# 0_96_OLED_FOR_1U.net
KiCad netlist of a schematic drawn in EAGLE
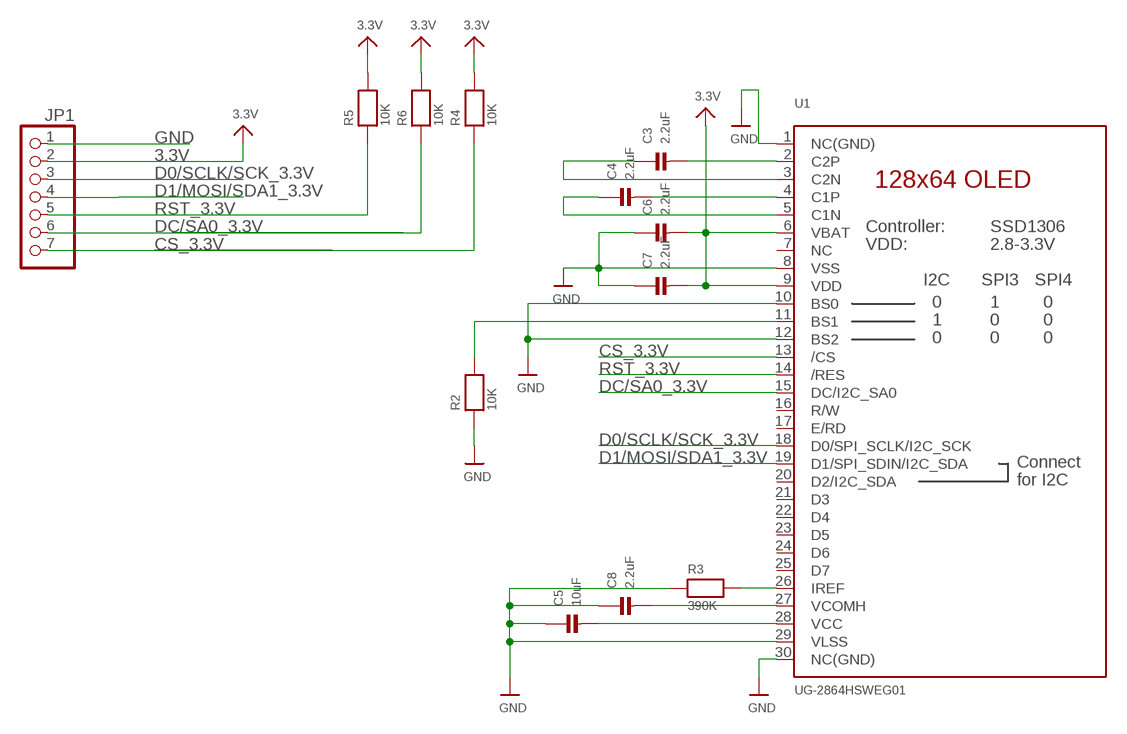
[diagram p0: schematic, sheet 1]

(export (version "E")
  (design (tool "Eeschema 10.0.6"))
  (components
    (comp (ref "C3")
      (value "2.2uF")
      (footprint "eagle-import:0603-MINI")
      (libsource (lib "eagle-import") (part "CAP_CERAMIC0603MINI"))
    )
    (comp (ref "C4")
      (value "2.2uF")
      (footprint "eagle-import:0603-MINI")
      (libsource (lib "eagle-import") (part "CAP_CERAMIC0603MINI"))
    )
    (comp (ref "C5")
      (value "10uF")
      (footprint "eagle-import:0603-MINI")
      (libsource (lib "eagle-import") (part "CAP_CERAMIC0603MINI"))
    )
    (comp (ref "C6")
      (value "2.2uF")
      (footprint "eagle-import:0603-MINI")
      (libsource (lib "eagle-import") (part "CAP_CERAMIC0603MINI"))
    )
    (comp (ref "C7")
      (value "2.2uF")
      (footprint "eagle-import:0603-MINI")
      (libsource (lib "eagle-import") (part "CAP_CERAMIC0603MINI"))
    )
    (comp (ref "C8")
      (value "2.2uF")
      (footprint "eagle-import:0603-MINI")
      (libsource (lib "eagle-import") (part "CAP_CERAMIC0603MINI"))
    )
    (comp (ref "JP1")
      (value "HEADER-1X7ROUND")
      (footprint "eagle-import:1X07_ROUND")
      (fields (field (name "SPICEPREFIX") "X"))
      (libsource (lib "eagle-import") (part "HEADER-1X7ROUND"))
    )
    (comp (ref "R2")
      (value "10K")
      (footprint "eagle-import:0603-MINI")
      (libsource (lib "eagle-import") (part "RESISTOR0603MINI"))
    )
    (comp (ref "R3")
      (value "390K")
      (footprint "eagle-import:0603-MINI")
      (libsource (lib "eagle-import") (part "RESISTOR0603MINI"))
    )
    (comp (ref "R4")
      (value "10K")
      (footprint "eagle-import:0603-MINI")
      (libsource (lib "eagle-import") (part "RESISTOR0603MINI"))
    )
    (comp (ref "R5")
      (value "10K")
      (footprint "eagle-import:0603-MINI")
      (libsource (lib "eagle-import") (part "RESISTOR0603MINI"))
    )
    (comp (ref "R6")
      (value "10K")
      (footprint "eagle-import:0603-MINI")
      (libsource (lib "eagle-import") (part "RESISTOR0603MINI"))
    )
    (comp (ref "U1")
      (value "UG-2864HSWEG01")
      (footprint "eagle-import:MICROBUILDER_UG-2864HSWEG01_0.96IN_WRAPAROUND")
      (libsource (lib "eagle-import") (part "MICROBUILDER_DISP_OLED_UG-2864HSWEG010.96{dblquote}"))
    )
  )
  (nets
    (net (code "1") (name "/CS_3.3V") (class "Default")
      (node (ref "JP1") (pin "7") (pinfunction "7_7") (pintype "passive"))
      (node (ref "R4") (pin "1") (pinfunction "1_1") (pintype "passive"))
      (node (ref "U1") (pin "13") (pinfunction "/CS_13") (pintype "input"))
    )
    (net (code "2") (name "/D0{slash}SCLK{slash}SCK_3.3V") (class "Default")
      (node (ref "JP1") (pin "3") (pinfunction "3_3") (pintype "passive"))
      (node (ref "U1") (pin "18") (pinfunction "D0/SPI_SCLK/I2C_SCK_18") (pintype "bidirectional"))
    )
    (net (code "3") (name "/D1{slash}MOSI{slash}SDA1_3.3V") (class "Default")
      (node (ref "JP1") (pin "4") (pinfunction "4_4") (pintype "passive"))
      (node (ref "U1") (pin "19") (pinfunction "D1/SPI_SDIN/I2C_SDA_19") (pintype "bidirectional"))
    )
    (net (code "4") (name "/DC{slash}SA0_3.3V") (class "Default")
      (node (ref "JP1") (pin "6") (pinfunction "6_6") (pintype "passive"))
      (node (ref "R6") (pin "1") (pinfunction "1_1") (pintype "passive"))
      (node (ref "U1") (pin "15") (pinfunction "DC/I2C_SA0_15") (pintype "input"))
    )
    (net (code "5") (name "/RST_3.3V") (class "Default")
      (node (ref "JP1") (pin "5") (pinfunction "5_5") (pintype "passive"))
      (node (ref "R5") (pin "1") (pinfunction "1_1") (pintype "passive"))
      (node (ref "U1") (pin "14") (pinfunction "/RES_14") (pintype "input"))
    )
    (net (code "6") (name "3.3V") (class "Default")
      (node (ref "C6") (pin "2") (pinfunction "P$2_2") (pintype "passive"))
      (node (ref "C7") (pin "2") (pinfunction "P$2_2") (pintype "passive"))
      (node (ref "JP1") (pin "2") (pinfunction "2_2") (pintype "passive"))
      (node (ref "R4") (pin "2") (pinfunction "2_2") (pintype "passive"))
      (node (ref "R5") (pin "2") (pinfunction "2_2") (pintype "passive"))
      (node (ref "R6") (pin "2") (pinfunction "2_2") (pintype "passive"))
      (node (ref "U1") (pin "6") (pinfunction "VBAT_6") (pintype "input"))
      (node (ref "U1") (pin "9") (pinfunction "VDD_9") (pintype "power_in"))
    )
    (net (code "7") (name "GND") (class "Default")
      (node (ref "C5") (pin "1") (pinfunction "P$1_1") (pintype "passive"))
      (node (ref "C6") (pin "1") (pinfunction "P$1_1") (pintype "passive"))
      (node (ref "C7") (pin "1") (pinfunction "P$1_1") (pintype "passive"))
      (node (ref "C8") (pin "1") (pinfunction "P$1_1") (pintype "passive"))
      (node (ref "JP1") (pin "1") (pinfunction "1_1") (pintype "passive"))
      (node (ref "R2") (pin "1") (pinfunction "1_1") (pintype "passive"))
      (node (ref "R3") (pin "1") (pinfunction "1_1") (pintype "passive"))
      (node (ref "U1") (pin "1") (pinfunction "NC(GND)_1") (pintype "input"))
      (node (ref "U1") (pin "10") (pinfunction "BS0_10") (pintype "input"))
      (node (ref "U1") (pin "12") (pinfunction "BS2_12") (pintype "input"))
      (node (ref "U1") (pin "29") (pinfunction "VLSS_29") (pintype "power_in"))
      (node (ref "U1") (pin "30") (pinfunction "NC(GND)_30") (pintype "input"))
      (node (ref "U1") (pin "8") (pinfunction "VSS_8") (pintype "power_in"))
    )
    (net (code "8") (name "Net-(C3-P$1)") (class "Default")
      (node (ref "C3") (pin "1") (pinfunction "P$1_1") (pintype "passive"))
      (node (ref "U1") (pin "3") (pinfunction "C2N_3") (pintype "input"))
    )
    (net (code "9") (name "Net-(C3-P$2)") (class "Default")
      (node (ref "C3") (pin "2") (pinfunction "P$2_2") (pintype "passive"))
      (node (ref "U1") (pin "2") (pinfunction "C2P_2") (pintype "input"))
    )
    (net (code "10") (name "Net-(C4-P$1)") (class "Default")
      (node (ref "C4") (pin "1") (pinfunction "P$1_1") (pintype "passive"))
      (node (ref "U1") (pin "5") (pinfunction "C1N_5") (pintype "input"))
    )
    (net (code "11") (name "Net-(C4-P$2)") (class "Default")
      (node (ref "C4") (pin "2") (pinfunction "P$2_2") (pintype "passive"))
      (node (ref "U1") (pin "4") (pinfunction "C1P_4") (pintype "input"))
    )
    (net (code "12") (name "Net-(C5-P$2)") (class "Default")
      (node (ref "C5") (pin "2") (pinfunction "P$2_2") (pintype "passive"))
      (node (ref "U1") (pin "28") (pinfunction "VCC_28") (pintype "power_in"))
    )
    (net (code "13") (name "Net-(C8-P$2)") (class "Default")
      (node (ref "C8") (pin "2") (pinfunction "P$2_2") (pintype "passive"))
      (node (ref "U1") (pin "27") (pinfunction "VCOMH_27") (pintype "output"))
    )
    (net (code "14") (name "Net-(U1-BS1)") (class "Default")
      (node (ref "R2") (pin "2") (pinfunction "2_2") (pintype "passive"))
      (node (ref "U1") (pin "11") (pinfunction "BS1_11") (pintype "input"))
    )
    (net (code "15") (name "Net-(U1-IREF)") (class "Default")
      (node (ref "R3") (pin "2") (pinfunction "2_2") (pintype "passive"))
      (node (ref "U1") (pin "26") (pinfunction "IREF_26") (pintype "input"))
    )
    (net (code "16") (name "unconnected-(U1-D2{slash}I2C_SDA-Pad20)") (class "Default")
      (node (ref "U1") (pin "20") (pinfunction "D2/I2C_SDA_20") (pintype "bidirectional"))
    )
    (net (code "17") (name "unconnected-(U1-D3-Pad21)") (class "Default")
      (node (ref "U1") (pin "21") (pinfunction "D3_21") (pintype "bidirectional"))
    )
    (net (code "18") (name "unconnected-(U1-D4-Pad22)") (class "Default")
      (node (ref "U1") (pin "22") (pinfunction "D4_22") (pintype "bidirectional"))
    )
    (net (code "19") (name "unconnected-(U1-D5-Pad23)") (class "Default")
      (node (ref "U1") (pin "23") (pinfunction "D5_23") (pintype "bidirectional"))
    )
    (net (code "20") (name "unconnected-(U1-D6-Pad24)") (class "Default")
      (node (ref "U1") (pin "24") (pinfunction "D6_24") (pintype "bidirectional"))
    )
    (net (code "21") (name "unconnected-(U1-D7-Pad25)") (class "Default")
      (node (ref "U1") (pin "25") (pinfunction "D7_25") (pintype "bidirectional"))
    )
    (net (code "22") (name "unconnected-(U1-E{slash}RD-Pad17)") (class "Default")
      (node (ref "U1") (pin "17") (pinfunction "E/RD_17") (pintype "input"))
    )
    (net (code "23") (name "unconnected-(U1-NC-Pad7)") (class "Default")
      (node (ref "U1") (pin "7") (pinfunction "NC_7") (pintype "no_connect"))
    )
    (net (code "24") (name "unconnected-(U1-R{slash}W-Pad16)") (class "Default")
      (node (ref "U1") (pin "16") (pinfunction "R/W_16") (pintype "input"))
    )
  )
)
